# V2_0.net
KiCad netlist of a schematic drawn in Altium Designer
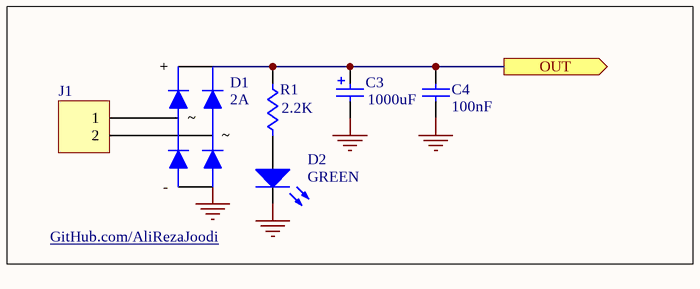
[diagram p0: V2.0.SchDoc]

(export (version "E")
  (design (tool "Eeschema 10.0.6"))
  (components
    (comp (ref "C3")
      (value "1000uF")
      (footprint "CAPPR5-10x12.5")
      (description "Polarized Capacitor (Radial)")
      (fields (field (name "MANUFACTURER") "Generic Components") (field (name "PUBLISHER") "Altium Limited"))
      (libsource (lib "Miscellaneous Devices") (part "Cap Pol1"))
    )
    (comp (ref "C4")
      (value "100nF")
      (footprint "CAPNTO2.54-3.05x1.78A")
      (description "Capacitor")
      (fields (field (name "MANUFACTURER") "Generic Components") (field (name "PUBLISHER") "Altium Limited"))
      (libsource (lib "Miscellaneous Devices") (part "Cap"))
    )
    (comp (ref "D1")
      (value "2A")
      (footprint "BRIDGE-1")
      (description "Full Wave Diode Bridge")
      (fields (field (name "MANUFACTURER") "Generic Components") (field (name "PUBLISHER") "Altium Limited"))
      (libsource (lib "my Libraries") (part "Bridge_1"))
    )
    (comp (ref "D2")
      (value "GREEN")
      (footprint "LED-5mm_Red")
      (description "Typical INFRARED GaAs LED")
      (fields (field (name "MANUFACTURER") "Generic Components") (field (name "PUBLISHER") "Altium Limited"))
      (libsource (lib "Miscellaneous Devices") (part "LED"))
    )
    (comp (ref "J1")
      (value "Header 2")
      (footprint "Fonics_2PIN_1")
      (description "Header, 2-Pin")
      (fields (field (name "PUBLISHER") "Altium Limited"))
      (libsource (lib "Miscellaneous Connectors") (part "Header 2"))
    )
    (comp (ref "R1")
      (value "2.2K")
      (footprint "AXIAL-0.4")
      (description "Resistor")
      (fields (field (name "MANUFACTURER") "Generic Components") (field (name "PUBLISHER") "Altium Limited"))
      (libsource (lib "Miscellaneous Devices") (part "Res1"))
    )
  )
  (nets
    (net (code "1") (name "/OUT") (class "Default")
      (node (ref "C3") (pin "1") (pinfunction "1_1") (pintype "passive"))
      (node (ref "C4") (pin "2") (pinfunction "2_2") (pintype "passive"))
      (node (ref "D1") (pin "3") (pinfunction "+_3") (pintype "passive"))
      (node (ref "R1") (pin "1") (pinfunction "1_1") (pintype "passive"))
    )
    (net (code "2") (name "GND") (class "Default")
      (node (ref "C3") (pin "2") (pinfunction "2_2") (pintype "passive"))
      (node (ref "C4") (pin "1") (pinfunction "1_1") (pintype "passive"))
      (node (ref "D1") (pin "1") (pinfunction "-_1") (pintype "passive"))
      (node (ref "D2") (pin "2") (pinfunction "K_2") (pintype "passive"))
    )
    (net (code "3") (name "Net-(D1-~-Pad2)") (class "Default")
      (node (ref "D1") (pin "2") (pinfunction "~_2") (pintype "passive"))
      (node (ref "J1") (pin "2") (pinfunction "2_2") (pintype "passive"))
    )
    (net (code "4") (name "Net-(D1-~-Pad4)") (class "Default")
      (node (ref "D1") (pin "4") (pinfunction "~_4") (pintype "passive"))
      (node (ref "J1") (pin "1") (pinfunction "1_1") (pintype "passive"))
    )
    (net (code "5") (name "Net-(D2-A)") (class "Default")
      (node (ref "D2") (pin "1") (pinfunction "A_1") (pintype "passive"))
      (node (ref "R1") (pin "2") (pinfunction "2_2") (pintype "passive"))
    )
  )
)
